# Booster_con.net
KiCad netlist of a schematic drawn in Altium Designer
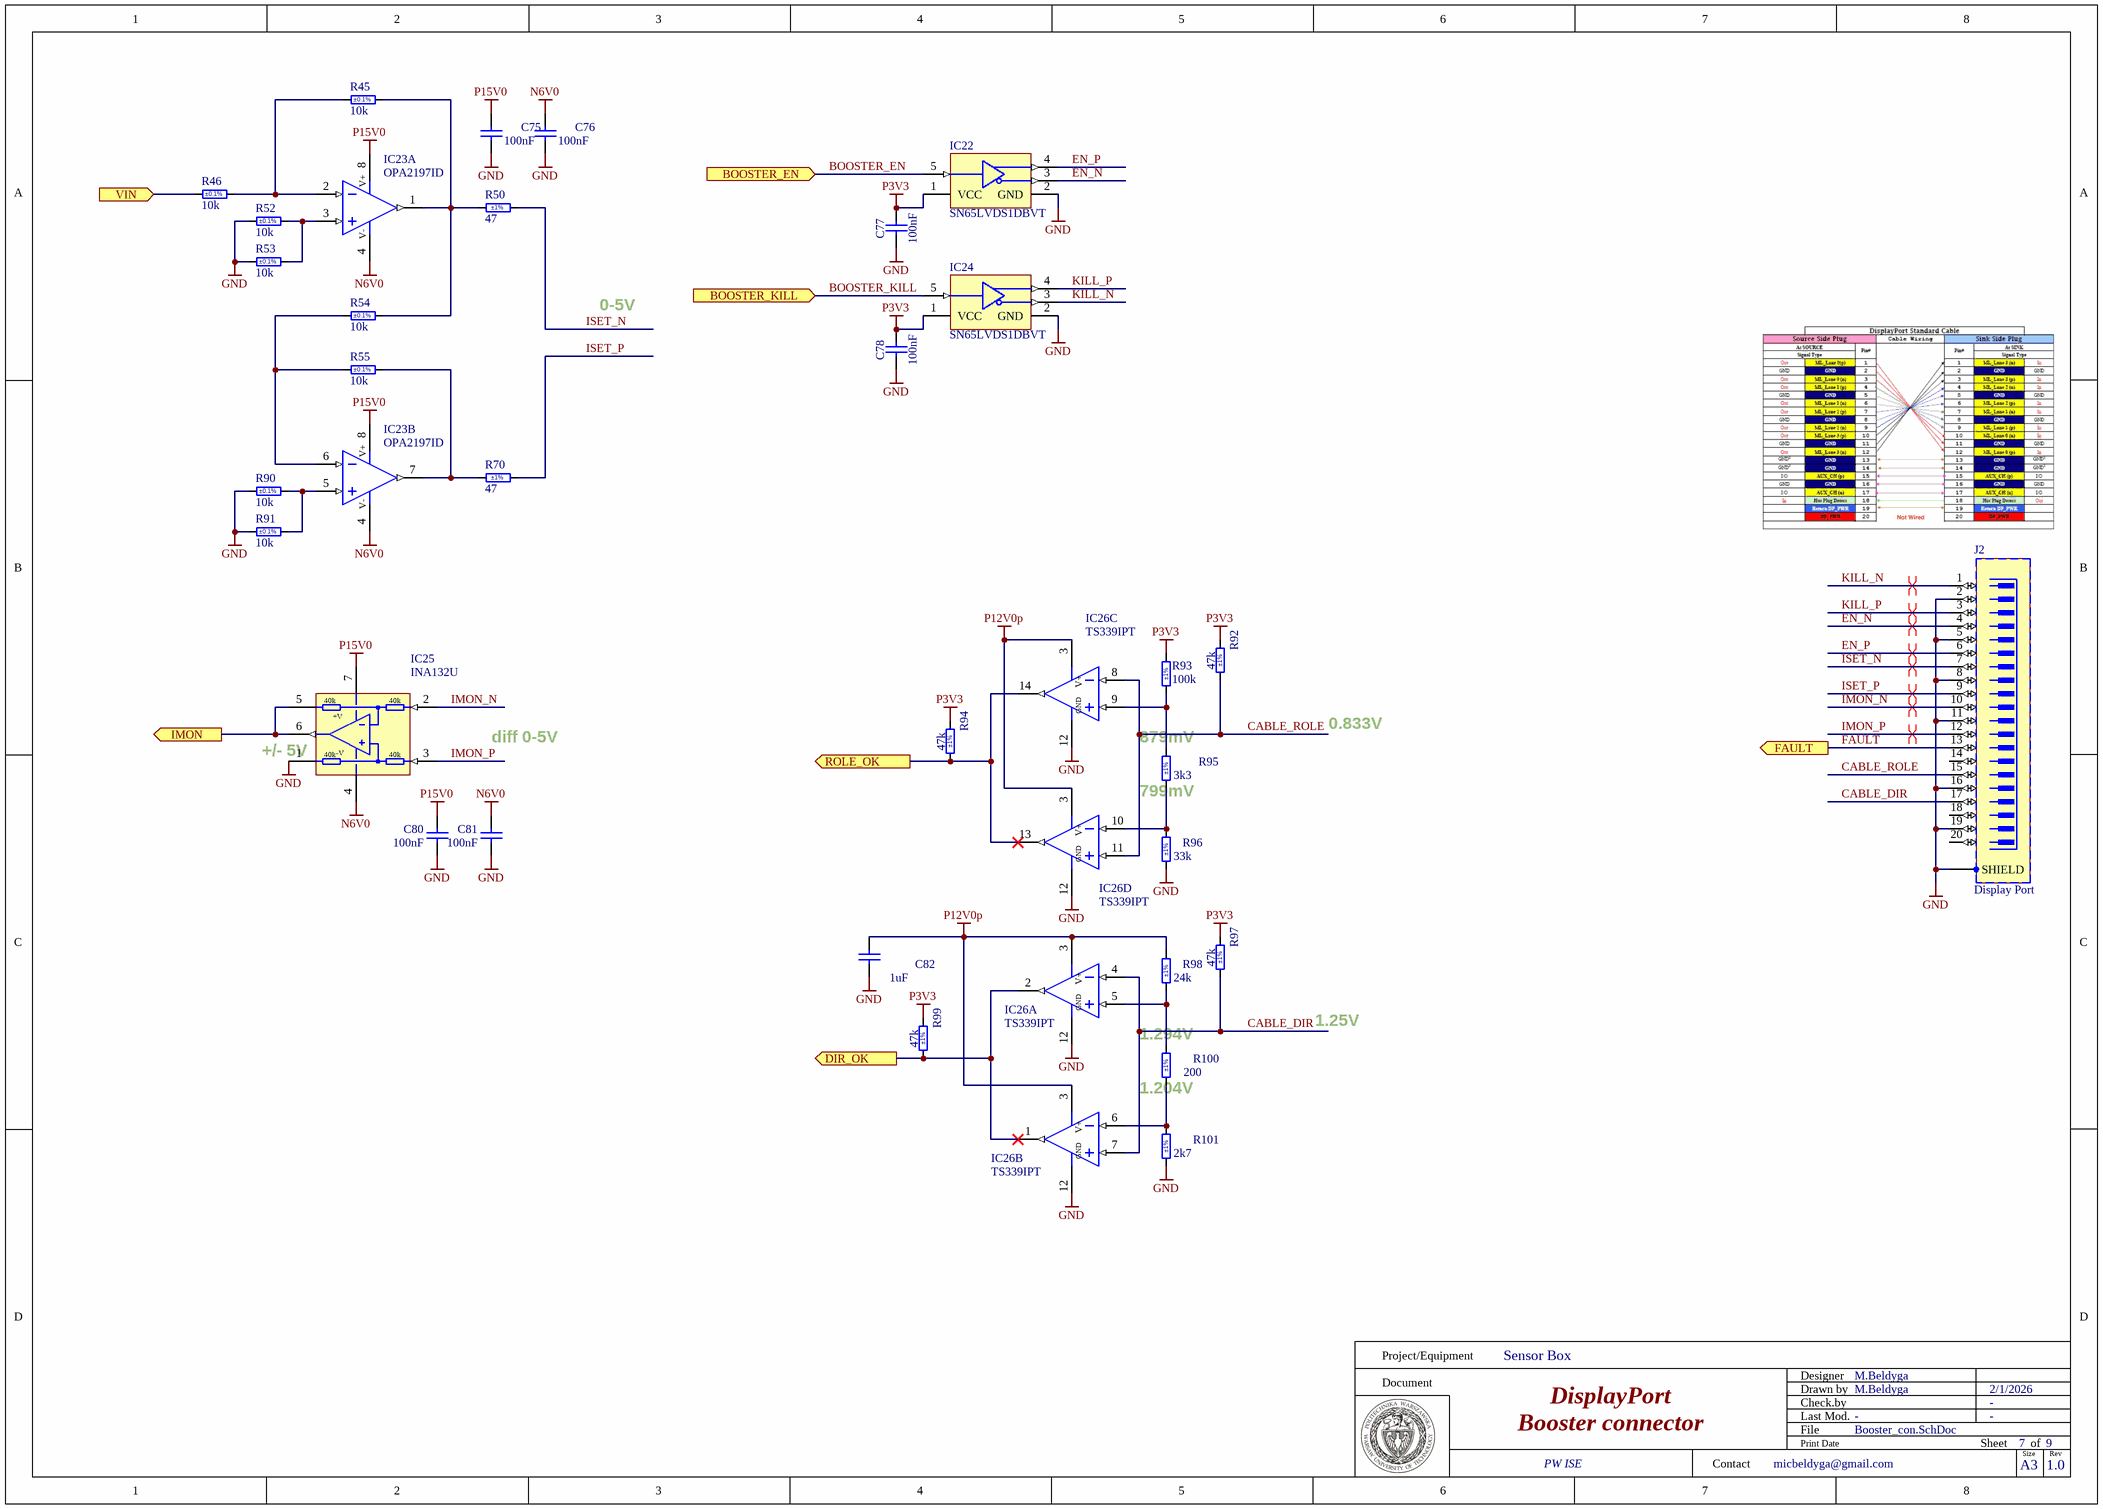
[diagram p0: Booster_con.SchDoc]

(export (version "E")
  (design (tool "Eeschema 10.0.6"))
  (components
    (comp (ref "C75")
      (value "100nF")
      (footprint "CAPC1005X55N")
      (description "Non-polarised capacitor")
      (fields
        (field (name "PART NUMBER") "CC0402_100NF_16V_10%_X5R")
        (field (name "VOLTAGE") "16V")
        (field (name "AUTHOR") "CERN DEM JLC")
      )
      (libsource (lib "Capacitors") (part "Capacitor - non polarized"))
    )
    (comp (ref "C76")
      (value "100nF")
      (footprint "CAPC1005X55N")
      (description "Non-polarised capacitor")
      (fields
        (field (name "PART NUMBER") "CC0402_100NF_16V_10%_X5R")
        (field (name "VOLTAGE") "16V")
        (field (name "AUTHOR") "CERN DEM JLC")
      )
      (libsource (lib "Capacitors") (part "Capacitor - non polarized"))
    )
    (comp (ref "C77")
      (value "100nF")
      (footprint "CAPC1005X55N")
      (description "Non-polarised capacitor")
      (fields
        (field (name "PART NUMBER") "CC0402_100NF_16V_10%_X7R")
        (field (name "VOLTAGE") "16V")
        (field (name "AUTHOR") "CERN DEM JLC")
      )
      (libsource (lib "Capacitors") (part "Capacitor - non polarized"))
    )
    (comp (ref "C78")
      (value "100nF")
      (footprint "CAPC1005X55N")
      (description "Non-polarised capacitor")
      (fields
        (field (name "PART NUMBER") "CC0402_100NF_16V_10%_X7R")
        (field (name "VOLTAGE") "16V")
        (field (name "AUTHOR") "CERN DEM JLC")
      )
      (libsource (lib "Capacitors") (part "Capacitor - non polarized"))
    )
    (comp (ref "C80")
      (value "100nF")
      (footprint "CAPC1005X55N")
      (description "Non-polarised capacitor")
      (fields
        (field (name "PART NUMBER") "CC0402_100NF_16V_10%_X5R")
        (field (name "VOLTAGE") "16V")
        (field (name "AUTHOR") "CERN DEM JLC")
      )
      (libsource (lib "Capacitors") (part "Capacitor - non polarized"))
    )
    (comp (ref "C81")
      (value "100nF")
      (footprint "CAPC1005X55N")
      (description "Non-polarised capacitor")
      (fields
        (field (name "PART NUMBER") "CC0402_100NF_16V_10%_X5R")
        (field (name "VOLTAGE") "16V")
        (field (name "AUTHOR") "CERN DEM JLC")
      )
      (libsource (lib "Capacitors") (part "Capacitor - non polarized"))
    )
    (comp (ref "C82")
      (value "1uF")
      (footprint "CAPC1005X55N")
      (description "Non-polarised capacitor")
      (fields
        (field (name "PART NUMBER") "CC0402_1UF_16V_10%_X5R")
        (field (name "VOLTAGE") "16V")
        (field (name "AUTHOR") "CERN DEM JLC")
      )
      (libsource (lib "Capacitors") (part "Capacitor - non polarized"))
    )
    (comp (ref "IC22")
      (value "SN65LVDS1DBVT")
      (footprint "SOT95P280X145-5N")
      (description "High-Speed Differential Line Driver")
      (fields
        (field (name "MANUFACTURER") "TEXAS INSTRUMENTS")
        (field (name "MANUFACTURER PART NUMBER") "SN65LVDS1DBV")
        (field (name "AUTHOR") "CERN DEM JLC")
      )
      (libsource (lib "ICs And Semiconductors") (part "SN65LVDS1DBV"))
    )
    (comp (ref "IC23")
      (value "OPA2197ID")
      (footprint "SOIC127P600X175-8N")
      (description "Dual Operational Amplifier")
      (fields (field (name "MANUFACTURER") "TEXAS INSTRUMENTS") (field (name "AUTHOR") "CERN DEM MR"))
      (libsource (lib "ICs And Semiconductors") (part "Operational Amplifier x2 Type1"))
    )
    (comp (ref "IC24")
      (value "SN65LVDS1DBVT")
      (footprint "SOT95P280X145-5N")
      (description "High-Speed Differential Line Driver")
      (fields
        (field (name "MANUFACTURER") "TEXAS INSTRUMENTS")
        (field (name "MANUFACTURER PART NUMBER") "SN65LVDS1DBV")
        (field (name "AUTHOR") "CERN DEM JLC")
      )
      (libsource (lib "ICs And Semiconductors") (part "SN65LVDS1DBV"))
    )
    (comp (ref "IC25")
      (value "INA132U")
      (footprint "SOIC127P600X175-8N")
      (description "High-Speed, Precision Difference Amplifier")
      (fields (field (name "MANUFACTURER") "TEXAS INSTRUMENTS") (field (name "AUTHOR") "CERN DEM JLC"))
      (libsource (lib "ICs And Semiconductors") (part "INA132"))
    )
    (comp (ref "IC26")
      (value "TS339IPT")
      (footprint "SOP65P640X120-14N")
      (description "Quad comparator")
      (fields (field (name "MANUFACTURER") "ST") (field (name "AUTHOR") "GK"))
      (libsource (lib "Amplifiers") (part "CMP_TS339"))
    )
    (comp (ref "J2")
      (value "Display Port")
      (footprint "MOLEX_47272-0001")
      (description "Connector Mini DisplayPort 20 Male + 1 Shield")
      (fields
        (field (name "PART NUMBER") "MOLEX_47272-0001")
        (field (name "MANUFACTURER") "MOLEX")
        (field (name "AUTHOR") "CERN DEM JLC")
      )
      (libsource (lib "Connectors") (part "Connector Mini DisplayPort 20 Male + 1 Shield"))
    )
    (comp (ref "R45")
      (value "10k")
      (footprint "RESC1005X35N")
      (description "Resistor - 0.1%")
      (fields
        (field (name "TOLERANCE") "±0.1%")
        (field (name "PART NUMBER") "R0402_10K_0.1%_0.063W_25PPM")
        (field (name "POWER") "0.063W")
        (field (name "AUTHOR") "CERN DEM JMW")
      )
      (libsource (lib "Resistors") (part "Resistor - 0.1%"))
    )
    (comp (ref "R46")
      (value "10k")
      (footprint "RESC1005X35N")
      (description "Resistor - 0.1%")
      (fields
        (field (name "TOLERANCE") "±0.1%")
        (field (name "PART NUMBER") "R0402_10K_0.1%_0.063W_25PPM")
        (field (name "POWER") "0.063W")
        (field (name "AUTHOR") "CERN DEM JMW")
      )
      (libsource (lib "Resistors") (part "Resistor - 0.1%"))
    )
    (comp (ref "R50")
      (value "47")
      (footprint "RESC1005X40N")
      (description "Resistor - 1%")
      (fields
        (field (name "TOLERANCE") "±1%")
        (field (name "PART NUMBER") "R0402_47R_1%_0.0625W_100PPM")
        (field (name "POWER") "0.0625W")
        (field (name "AUTHOR") "CERN DEM JLC")
      )
      (libsource (lib "Resistors") (part "Resistor - 1%"))
    )
    (comp (ref "R52")
      (value "10k")
      (footprint "RESC1005X35N")
      (description "Resistor - 0.1%")
      (fields
        (field (name "TOLERANCE") "±0.1%")
        (field (name "PART NUMBER") "R0402_10K_0.1%_0.063W_25PPM")
        (field (name "POWER") "0.063W")
        (field (name "AUTHOR") "CERN DEM JMW")
      )
      (libsource (lib "Resistors") (part "Resistor - 0.1%"))
    )
    (comp (ref "R53")
      (value "10k")
      (footprint "RESC1005X35N")
      (description "Resistor - 0.1%")
      (fields
        (field (name "TOLERANCE") "±0.1%")
        (field (name "PART NUMBER") "R0402_10K_0.1%_0.063W_25PPM")
        (field (name "POWER") "0.063W")
        (field (name "AUTHOR") "CERN DEM JMW")
      )
      (libsource (lib "Resistors") (part "Resistor - 0.1%"))
    )
    (comp (ref "R54")
      (value "10k")
      (footprint "RESC1005X35N")
      (description "Resistor - 0.1%")
      (fields
        (field (name "TOLERANCE") "±0.1%")
        (field (name "PART NUMBER") "R0402_10K_0.1%_0.063W_25PPM")
        (field (name "POWER") "0.063W")
        (field (name "AUTHOR") "CERN DEM JMW")
      )
      (libsource (lib "Resistors") (part "Resistor - 0.1%"))
    )
    (comp (ref "R55")
      (value "10k")
      (footprint "RESC1005X35N")
      (description "Resistor - 0.1%")
      (fields
        (field (name "TOLERANCE") "±0.1%")
        (field (name "PART NUMBER") "R0402_10K_0.1%_0.063W_25PPM")
        (field (name "POWER") "0.063W")
        (field (name "AUTHOR") "CERN DEM JMW")
      )
      (libsource (lib "Resistors") (part "Resistor - 0.1%"))
    )
    (comp (ref "R70")
      (value "47")
      (footprint "RESC1005X40N")
      (description "Resistor - 1%")
      (fields
        (field (name "TOLERANCE") "±1%")
        (field (name "PART NUMBER") "R0402_47R_1%_0.0625W_100PPM")
        (field (name "POWER") "0.0625W")
        (field (name "AUTHOR") "CERN DEM JLC")
      )
      (libsource (lib "Resistors") (part "Resistor - 1%"))
    )
    (comp (ref "R90")
      (value "10k")
      (footprint "RESC1005X35N")
      (description "Resistor - 0.1%")
      (fields
        (field (name "TOLERANCE") "±0.1%")
        (field (name "PART NUMBER") "R0402_10K_0.1%_0.063W_25PPM")
        (field (name "POWER") "0.063W")
        (field (name "AUTHOR") "CERN DEM JMW")
      )
      (libsource (lib "Resistors") (part "Resistor - 0.1%"))
    )
    (comp (ref "R91")
      (value "10k")
      (footprint "RESC1005X35N")
      (description "Resistor - 0.1%")
      (fields
        (field (name "TOLERANCE") "±0.1%")
        (field (name "PART NUMBER") "R0402_10K_0.1%_0.063W_25PPM")
        (field (name "POWER") "0.063W")
        (field (name "AUTHOR") "CERN DEM JMW")
      )
      (libsource (lib "Resistors") (part "Resistor - 0.1%"))
    )
    (comp (ref "R92")
      (value "47k")
      (footprint "RESC1005X40N")
      (description "Resistor - 1%")
      (fields
        (field (name "TOLERANCE") "±1%")
        (field (name "PART NUMBER") "R0402_47K_1%_0.0625W_100PPM")
        (field (name "POWER") "0.0625W")
        (field (name "AUTHOR") "CERN DEM JLC")
      )
      (libsource (lib "Resistors") (part "Resistor - 1%"))
    )
    (comp (ref "R93")
      (value "100k")
      (footprint "RESC1005X40N")
      (description "Resistor - 1%")
      (fields
        (field (name "TOLERANCE") "±1%")
        (field (name "PART NUMBER") "R0402_100K_1%_0.0625W_100PPM")
        (field (name "POWER") "0.0625W")
        (field (name "AUTHOR") "CERN DEM JLC")
      )
      (libsource (lib "Resistors") (part "Resistor - 1%"))
    )
    (comp (ref "R94")
      (value "47k")
      (footprint "RESC1005X40N")
      (description "Resistor - 1%")
      (fields
        (field (name "TOLERANCE") "±1%")
        (field (name "PART NUMBER") "R0402_47K_1%_0.0625W_100PPM")
        (field (name "POWER") "0.0625W")
        (field (name "AUTHOR") "CERN DEM JLC")
      )
      (libsource (lib "Resistors") (part "Resistor - 1%"))
    )
    (comp (ref "R95")
      (value "3k3")
      (footprint "RESC1005X40N")
      (description "Resistor - 1%")
      (fields
        (field (name "TOLERANCE") "±1%")
        (field (name "PART NUMBER") "R0402_3K3_1%_0.0625W_100PPM")
        (field (name "POWER") "0.0625W")
        (field (name "AUTHOR") "CERN DEM JLC")
      )
      (libsource (lib "Resistors") (part "Resistor - 1%"))
    )
    (comp (ref "R96")
      (value "33k")
      (footprint "RESC1005X40N")
      (description "Resistor - 1%")
      (fields
        (field (name "TOLERANCE") "±1%")
        (field (name "PART NUMBER") "R0402_33K_1%_0.0625W_100PPM")
        (field (name "POWER") "0.0625W")
        (field (name "AUTHOR") "CERN DEM JLC")
      )
      (libsource (lib "Resistors") (part "Resistor - 1%"))
    )
    (comp (ref "R97")
      (value "47k")
      (footprint "RESC1005X40N")
      (description "Resistor - 1%")
      (fields
        (field (name "TOLERANCE") "±1%")
        (field (name "PART NUMBER") "R0402_47K_1%_0.0625W_100PPM")
        (field (name "POWER") "0.0625W")
        (field (name "AUTHOR") "CERN DEM JLC")
      )
      (libsource (lib "Resistors") (part "Resistor - 1%"))
    )
    (comp (ref "R98")
      (value "24k")
      (footprint "RESC1005X40N")
      (description "Resistor - 1%")
      (fields
        (field (name "TOLERANCE") "±1%")
        (field (name "PART NUMBER") "R0402_24K_1%_0.0625W_100PPM")
        (field (name "POWER") "0.0625W")
        (field (name "AUTHOR") "CERN DEM JLC")
      )
      (libsource (lib "Resistors") (part "Resistor - 1%"))
    )
    (comp (ref "R99")
      (value "47k")
      (footprint "RESC1005X40N")
      (description "Resistor - 1%")
      (fields
        (field (name "TOLERANCE") "±1%")
        (field (name "PART NUMBER") "R0402_47K_1%_0.0625W_100PPM")
        (field (name "POWER") "0.0625W")
        (field (name "AUTHOR") "CERN DEM JLC")
      )
      (libsource (lib "Resistors") (part "Resistor - 1%"))
    )
    (comp (ref "R100")
      (value "200")
      (footprint "RESC1608X55N")
      (description "Resistor - 1%")
      (fields
        (field (name "TOLERANCE") "±1%")
        (field (name "PART NUMBER") "R0603_200R_1%_0.1W_100PPM")
        (field (name "POWER") "0.1W")
        (field (name "AUTHOR") "CERN DEM JLC")
      )
      (libsource (lib "Resistors") (part "Resistor - 1%"))
    )
    (comp (ref "R101")
      (value "2k7")
      (footprint "RESC1005X40N")
      (description "Resistor - 1%")
      (fields
        (field (name "TOLERANCE") "±1%")
        (field (name "PART NUMBER") "R0402_2K7_1%_0.0625W_100PPM")
        (field (name "POWER") "0.0625W")
        (field (name "AUTHOR") "CERN DEM HF")
      )
      (libsource (lib "Resistors") (part "Resistor - 1%"))
    )
  )
  (nets
    (net (code "1") (name "/BOOSTER_EN") (class "Default")
      (node (ref "IC22") (pin "5") (pinfunction "R_5") (pintype "input"))
    )
    (net (code "2") (name "/BOOSTER_KILL") (class "Default")
      (node (ref "IC24") (pin "5") (pinfunction "R_5") (pintype "input"))
    )
    (net (code "3") (name "/CABLE_DIR") (class "Default")
      (node (ref "IC26") (pin "4") (pinfunction "IN-_4") (pintype "input"))
      (node (ref "IC26") (pin "7") (pinfunction "IN+_7") (pintype "input"))
      (node (ref "J2") (pin "17") (pinfunction "17_17") (pintype "bidirectional"))
      (node (ref "R97") (pin "1") (pinfunction "1_1") (pintype "passive"))
    )
    (net (code "4") (name "/CABLE_ROLE") (class "Default")
      (node (ref "IC26") (pin "11") (pinfunction "IN+_11") (pintype "input"))
      (node (ref "IC26") (pin "8") (pinfunction "IN-_8") (pintype "input"))
      (node (ref "J2") (pin "15") (pinfunction "15_15") (pintype "bidirectional"))
      (node (ref "R92") (pin "1") (pinfunction "1_1") (pintype "passive"))
    )
    (net (code "5") (name "/DIR_OK") (class "Default")
      (node (ref "IC26") (pin "1") (pinfunction "OUT_1") (pintype "output"))
      (node (ref "IC26") (pin "2") (pinfunction "OUT_2") (pintype "output"))
      (node (ref "R99") (pin "1") (pinfunction "1_1") (pintype "passive"))
    )
    (net (code "6") (name "/EN_N") (class "Default")
      (node (ref "IC22") (pin "3") (pinfunction "A_3") (pintype "output"))
      (node (ref "J2") (pin "4") (pinfunction "4_4") (pintype "bidirectional"))
    )
    (net (code "7") (name "/EN_P") (class "Default")
      (node (ref "IC22") (pin "4") (pinfunction "B_4") (pintype "output"))
      (node (ref "J2") (pin "6") (pinfunction "6_6") (pintype "bidirectional"))
    )
    (net (code "8") (name "/FAULT") (class "Default")
      (node (ref "J2") (pin "13") (pinfunction "13_13") (pintype "bidirectional"))
    )
    (net (code "9") (name "/IMON") (class "Default")
      (node (ref "IC25") (pin "5") (pinfunction "SENS_5") (pintype "passive"))
      (node (ref "IC25") (pin "6") (pinfunction "OUT_6") (pintype "output"))
    )
    (net (code "10") (name "/IMON_N") (class "Default")
      (node (ref "IC25") (pin "2") (pinfunction "IN-_2") (pintype "input"))
      (node (ref "J2") (pin "10") (pinfunction "10_10") (pintype "bidirectional"))
    )
    (net (code "11") (name "/IMON_P") (class "Default")
      (node (ref "IC25") (pin "3") (pinfunction "IN+_3") (pintype "input"))
      (node (ref "J2") (pin "12") (pinfunction "12_12") (pintype "bidirectional"))
    )
    (net (code "12") (name "/ISET_N") (class "Default")
      (node (ref "J2") (pin "7") (pinfunction "7_7") (pintype "bidirectional"))
      (node (ref "R50") (pin "2") (pinfunction "2_2") (pintype "passive"))
    )
    (net (code "13") (name "/ISET_P") (class "Default")
      (node (ref "J2") (pin "9") (pinfunction "9_9") (pintype "bidirectional"))
      (node (ref "R70") (pin "2") (pinfunction "2_2") (pintype "passive"))
    )
    (net (code "14") (name "/KILL_N") (class "Default")
      (node (ref "IC24") (pin "3") (pinfunction "A_3") (pintype "output"))
      (node (ref "J2") (pin "1") (pinfunction "1_1") (pintype "bidirectional"))
    )
    (net (code "15") (name "/KILL_P") (class "Default")
      (node (ref "IC24") (pin "4") (pinfunction "B_4") (pintype "output"))
      (node (ref "J2") (pin "3") (pinfunction "3_3") (pintype "bidirectional"))
    )
    (net (code "16") (name "/ROLE_OK") (class "Default")
      (node (ref "IC26") (pin "13") (pinfunction "OUT_13") (pintype "output"))
      (node (ref "IC26") (pin "14") (pinfunction "OUT_14") (pintype "output"))
      (node (ref "R94") (pin "1") (pinfunction "1_1") (pintype "passive"))
    )
    (net (code "17") (name "/VIN") (class "Default")
      (node (ref "R46") (pin "1") (pinfunction "1_1") (pintype "passive"))
    )
    (net (code "18") (name "GND") (class "Default")
      (node (ref "C75") (pin "1") (pinfunction "1_1") (pintype "passive"))
      (node (ref "C76") (pin "1") (pinfunction "1_1") (pintype "passive"))
      (node (ref "C77") (pin "1") (pinfunction "1_1") (pintype "passive"))
      (node (ref "C78") (pin "1") (pinfunction "1_1") (pintype "passive"))
      (node (ref "C80") (pin "1") (pinfunction "1_1") (pintype "passive"))
      (node (ref "C81") (pin "1") (pinfunction "1_1") (pintype "passive"))
      (node (ref "C82") (pin "1") (pinfunction "1_1") (pintype "passive"))
      (node (ref "IC22") (pin "2") (pinfunction "GND_2") (pintype "power_in"))
      (node (ref "IC24") (pin "2") (pinfunction "GND_2") (pintype "power_in"))
      (node (ref "IC25") (pin "1") (pinfunction "REF_1") (pintype "passive"))
      (node (ref "IC26") (pin "12") (pinfunction "GND_12") (pintype "power_in"))
      (node (ref "J2") (pin "11") (pinfunction "11_11") (pintype "bidirectional"))
      (node (ref "J2") (pin "16") (pinfunction "16_16") (pintype "bidirectional"))
      (node (ref "J2") (pin "19") (pinfunction "19_19") (pintype "bidirectional"))
      (node (ref "J2") (pin "2") (pinfunction "2_2") (pintype "bidirectional"))
      (node (ref "J2") (pin "5") (pinfunction "5_5") (pintype "bidirectional"))
      (node (ref "J2") (pin "8") (pinfunction "8_8") (pintype "bidirectional"))
      (node (ref "J2") (pin "SHIELD") (pinfunction "SHIELD_SHIELD") (pintype "power_in"))
      (node (ref "R101") (pin "1") (pinfunction "1_1") (pintype "passive"))
      (node (ref "R52") (pin "1") (pinfunction "1_1") (pintype "passive"))
      (node (ref "R53") (pin "1") (pinfunction "1_1") (pintype "passive"))
      (node (ref "R90") (pin "1") (pinfunction "1_1") (pintype "passive"))
      (node (ref "R91") (pin "1") (pinfunction "1_1") (pintype "passive"))
      (node (ref "R96") (pin "1") (pinfunction "1_1") (pintype "passive"))
    )
    (net (code "19") (name "N6V0") (class "Default")
      (node (ref "C76") (pin "2") (pinfunction "2_2") (pintype "passive"))
      (node (ref "C81") (pin "2") (pinfunction "2_2") (pintype "passive"))
      (node (ref "IC23") (pin "4") (pinfunction "V-_4") (pintype "power_in"))
      (node (ref "IC25") (pin "4") (pinfunction "-VEE_4") (pintype "power_in"))
    )
    (net (code "20") (name "Net-(IC23A-IN+)") (class "Default")
      (node (ref "IC23") (pin "3") (pinfunction "IN+_3") (pintype "input"))
      (node (ref "R52") (pin "2") (pinfunction "2_2") (pintype "passive"))
      (node (ref "R53") (pin "2") (pinfunction "2_2") (pintype "passive"))
    )
    (net (code "21") (name "Net-(IC23A-IN-)") (class "Default")
      (node (ref "IC23") (pin "2") (pinfunction "IN-_2") (pintype "input"))
      (node (ref "R45") (pin "2") (pinfunction "2_2") (pintype "passive"))
      (node (ref "R46") (pin "2") (pinfunction "2_2") (pintype "passive"))
    )
    (net (code "22") (name "Net-(IC23A-OUT)") (class "Default")
      (node (ref "IC23") (pin "1") (pinfunction "OUT_1") (pintype "output"))
      (node (ref "R45") (pin "1") (pinfunction "1_1") (pintype "passive"))
      (node (ref "R50") (pin "1") (pinfunction "1_1") (pintype "passive"))
      (node (ref "R54") (pin "2") (pinfunction "2_2") (pintype "passive"))
    )
    (net (code "23") (name "Net-(IC23B-IN+)") (class "Default")
      (node (ref "IC23") (pin "5") (pinfunction "IN+_5") (pintype "input"))
      (node (ref "R90") (pin "2") (pinfunction "2_2") (pintype "passive"))
      (node (ref "R91") (pin "2") (pinfunction "2_2") (pintype "passive"))
    )
    (net (code "24") (name "Net-(IC23B-IN-)") (class "Default")
      (node (ref "IC23") (pin "6") (pinfunction "IN-_6") (pintype "input"))
      (node (ref "R54") (pin "1") (pinfunction "1_1") (pintype "passive"))
      (node (ref "R55") (pin "2") (pinfunction "2_2") (pintype "passive"))
    )
    (net (code "25") (name "Net-(IC23B-OUT)") (class "Default")
      (node (ref "IC23") (pin "7") (pinfunction "OUT_7") (pintype "output"))
      (node (ref "R55") (pin "1") (pinfunction "1_1") (pintype "passive"))
      (node (ref "R70") (pin "1") (pinfunction "1_1") (pintype "passive"))
    )
    (net (code "26") (name "Net-(IC26A-IN+)") (class "Default")
      (node (ref "IC26") (pin "5") (pinfunction "IN+_5") (pintype "input"))
      (node (ref "R100") (pin "2") (pinfunction "2_2") (pintype "passive"))
      (node (ref "R98") (pin "1") (pinfunction "1_1") (pintype "passive"))
    )
    (net (code "27") (name "Net-(IC26B-IN-)") (class "Default")
      (node (ref "IC26") (pin "6") (pinfunction "IN-_6") (pintype "input"))
      (node (ref "R100") (pin "1") (pinfunction "1_1") (pintype "passive"))
      (node (ref "R101") (pin "2") (pinfunction "2_2") (pintype "passive"))
    )
    (net (code "28") (name "Net-(IC26C-IN+)") (class "Default")
      (node (ref "IC26") (pin "9") (pinfunction "IN+_9") (pintype "input"))
      (node (ref "R93") (pin "1") (pinfunction "1_1") (pintype "passive"))
      (node (ref "R95") (pin "2") (pinfunction "2_2") (pintype "passive"))
    )
    (net (code "29") (name "Net-(IC26D-IN-)") (class "Default")
      (node (ref "IC26") (pin "10") (pinfunction "IN-_10") (pintype "input"))
      (node (ref "R95") (pin "1") (pinfunction "1_1") (pintype "passive"))
      (node (ref "R96") (pin "2") (pinfunction "2_2") (pintype "passive"))
    )
    (net (code "30") (name "P3V3") (class "Default")
      (node (ref "C77") (pin "2") (pinfunction "2_2") (pintype "passive"))
      (node (ref "C78") (pin "2") (pinfunction "2_2") (pintype "passive"))
      (node (ref "IC22") (pin "1") (pinfunction "VCC_1") (pintype "power_in"))
      (node (ref "IC24") (pin "1") (pinfunction "VCC_1") (pintype "power_in"))
      (node (ref "R92") (pin "2") (pinfunction "2_2") (pintype "passive"))
      (node (ref "R93") (pin "2") (pinfunction "2_2") (pintype "passive"))
      (node (ref "R94") (pin "2") (pinfunction "2_2") (pintype "passive"))
      (node (ref "R97") (pin "2") (pinfunction "2_2") (pintype "passive"))
      (node (ref "R99") (pin "2") (pinfunction "2_2") (pintype "passive"))
    )
    (net (code "31") (name "P12V0p") (class "Default")
      (node (ref "C82") (pin "2") (pinfunction "2_2") (pintype "passive"))
      (node (ref "IC26") (pin "3") (pinfunction "V+_3") (pintype "power_in"))
      (node (ref "R98") (pin "2") (pinfunction "2_2") (pintype "passive"))
    )
    (net (code "32") (name "P15V0") (class "Default")
      (node (ref "C75") (pin "2") (pinfunction "2_2") (pintype "passive"))
      (node (ref "C80") (pin "2") (pinfunction "2_2") (pintype "passive"))
      (node (ref "IC23") (pin "8") (pinfunction "V+_8") (pintype "power_in"))
      (node (ref "IC25") (pin "7") (pinfunction "+VCC_7") (pintype "power_in"))
    )
    (net (code "33") (name "unconnected-(J2-Pad14)") (class "Default")
      (node (ref "J2") (pin "14") (pinfunction "14_14") (pintype "bidirectional"))
    )
    (net (code "34") (name "unconnected-(J2-Pad18)") (class "Default")
      (node (ref "J2") (pin "18") (pinfunction "18_18") (pintype "bidirectional"))
    )
    (net (code "35") (name "unconnected-(J2-Pad20)") (class "Default")
      (node (ref "J2") (pin "20") (pinfunction "20_20") (pintype "bidirectional"))
    )
  )
)
